# Alimentatore_Banco.net
KiCad netlist of a schematic drawn in EAGLE
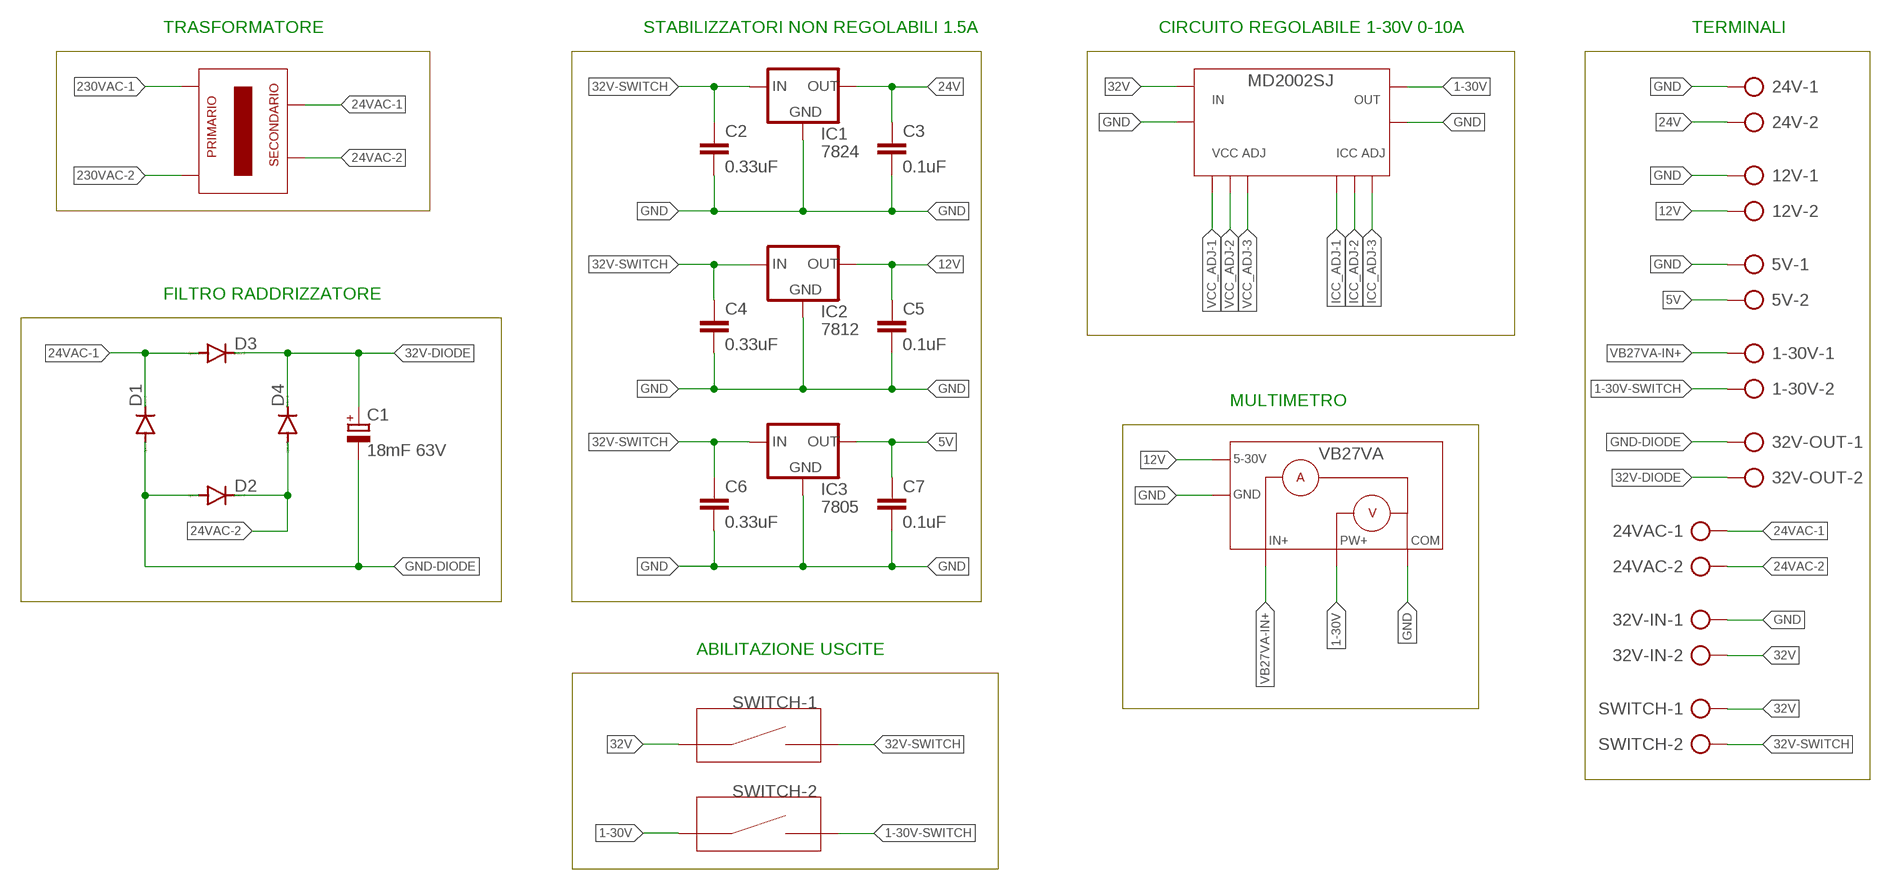
[diagram p0: schematic, sheet 1]

(export (version "E")
  (design (tool "Eeschema 10.0.6"))
  (components
    (comp (ref "1-30V")
      (value "SMKDSP_1,5/2")
      (footprint "eagle-import:SMKDSP_1,5_2")
      (fields (field (name "MF") "FARNELL") (field (name "MPN") "1733570"))
      (libsource (lib "eagle-import") (part "SMKDSP_1,5/2"))
    )
    (comp (ref "5V")
      (value "SMKDSP_1,5/2")
      (footprint "eagle-import:SMKDSP_1,5_2")
      (fields (field (name "MF") "FARNELL") (field (name "MPN") "1733570"))
      (libsource (lib "eagle-import") (part "SMKDSP_1,5/2"))
    )
    (comp (ref "12V")
      (value "SMKDSP_1,5/2")
      (footprint "eagle-import:SMKDSP_1,5_2")
      (fields (field (name "MF") "FARNELL") (field (name "MPN") "1733570"))
      (libsource (lib "eagle-import") (part "SMKDSP_1,5/2"))
    )
    (comp (ref "24V")
      (value "SMKDSP_1,5/2")
      (footprint "eagle-import:SMKDSP_1,5_2")
      (fields (field (name "MF") "FARNELL") (field (name "MPN") "1733570"))
      (libsource (lib "eagle-import") (part "SMKDSP_1,5/2"))
    )
    (comp (ref "24VAC")
      (value "SMKDSP_1,5/2")
      (footprint "eagle-import:SMKDSP_1,5_2")
      (fields (field (name "MF") "FARNELL") (field (name "MPN") "1733570"))
      (libsource (lib "eagle-import") (part "SMKDSP_1,5/2"))
    )
    (comp (ref "32V-IN")
      (value "SMKDSP_1,5/2")
      (footprint "eagle-import:SMKDSP_1,5_2")
      (fields (field (name "MF") "FARNELL") (field (name "MPN") "1733570"))
      (libsource (lib "eagle-import") (part "SMKDSP_1,5/2"))
    )
    (comp (ref "32V-OUT")
      (value "SMKDSP_1,5/2")
      (footprint "eagle-import:SMKDSP_1,5_2")
      (fields (field (name "MF") "FARNELL") (field (name "MPN") "1733570"))
      (libsource (lib "eagle-import") (part "SMKDSP_1,5/2"))
    )
    (comp (ref "C1")
      (value "18mF 63V")
      (footprint "eagle-import:E5-10,5")
      (libsource (lib "eagle-import") (part "CPOL-EUE5-10.5"))
    )
    (comp (ref "C2")
      (value "0.33uF")
      (footprint "eagle-import:C025-025X050")
      (libsource (lib "eagle-import") (part "C-EU025-025X050"))
    )
    (comp (ref "C3")
      (value "0.1uF")
      (footprint "eagle-import:C025-025X050")
      (libsource (lib "eagle-import") (part "C-EU025-025X050"))
    )
    (comp (ref "C4")
      (value "0.33uF")
      (footprint "eagle-import:C025-025X050")
      (libsource (lib "eagle-import") (part "C-EU025-025X050"))
    )
    (comp (ref "C5")
      (value "0.1uF")
      (footprint "eagle-import:C025-025X050")
      (libsource (lib "eagle-import") (part "C-EU025-025X050"))
    )
    (comp (ref "C6")
      (value "0.33uF")
      (footprint "eagle-import:C025-025X050")
      (libsource (lib "eagle-import") (part "C-EU025-025X050"))
    )
    (comp (ref "C7")
      (value "0.1uF")
      (footprint "eagle-import:C025-025X050")
      (libsource (lib "eagle-import") (part "C-EU025-025X050"))
    )
    (comp (ref "D1")
      (value "BY550")
      (footprint "eagle-import:DO27-15")
      (libsource (lib "eagle-import") (part "BY550"))
    )
    (comp (ref "D2")
      (value "BY550")
      (footprint "eagle-import:DO27-15")
      (libsource (lib "eagle-import") (part "BY550"))
    )
    (comp (ref "D3")
      (value "BY550")
      (footprint "eagle-import:DO27-15")
      (libsource (lib "eagle-import") (part "BY550"))
    )
    (comp (ref "D4")
      (value "BY550")
      (footprint "eagle-import:DO27-15")
      (libsource (lib "eagle-import") (part "BY550"))
    )
    (comp (ref "IC1")
      (value "7824")
      (footprint "eagle-import:78XXS")
      (libsource (lib "eagle-import") (part "78XXS"))
    )
    (comp (ref "IC2")
      (value "7812")
      (footprint "eagle-import:78XXS")
      (libsource (lib "eagle-import") (part "78XXS"))
    )
    (comp (ref "IC3")
      (value "7805")
      (footprint "eagle-import:78XXS")
      (libsource (lib "eagle-import") (part "78XXS"))
    )
    (comp (ref "SWITCH")
      (value "SMKDSP_1,5/2")
      (footprint "eagle-import:SMKDSP_1,5_2")
      (fields (field (name "MF") "FARNELL") (field (name "MPN") "1733570"))
      (libsource (lib "eagle-import") (part "SMKDSP_1,5/2"))
    )
  )
  (nets
    (net (code "2") (name "1-30V-SWITCH") (class "Default")
      (node (ref "1-30V") (pin "2") (pinfunction "KL_2") (pintype "passive"))
    )
    (net (code "3") (name "5V") (class "Default")
      (node (ref "5V") (pin "2") (pinfunction "KL_2") (pintype "passive"))
      (node (ref "C7") (pin "1") (pinfunction "1_1") (pintype "passive"))
      (node (ref "IC3") (pin "OUT") (pinfunction "OUT_OUT") (pintype "passive"))
    )
    (net (code "4") (name "12V") (class "Default")
      (node (ref "12V") (pin "2") (pinfunction "KL_2") (pintype "passive"))
      (node (ref "C5") (pin "1") (pinfunction "1_1") (pintype "passive"))
      (node (ref "IC2") (pin "OUT") (pinfunction "OUT_OUT") (pintype "passive"))
    )
    (net (code "5") (name "24V") (class "Default")
      (node (ref "24V") (pin "2") (pinfunction "KL_2") (pintype "passive"))
      (node (ref "C3") (pin "1") (pinfunction "1_1") (pintype "passive"))
      (node (ref "IC1") (pin "OUT") (pinfunction "OUT_OUT") (pintype "passive"))
    )
    (net (code "6") (name "24VAC-1") (class "Default")
      (node (ref "24VAC") (pin "1") (pinfunction "KL_1") (pintype "passive"))
      (node (ref "D1") (pin "C") (pinfunction "C_C") (pintype "passive"))
      (node (ref "D3") (pin "A") (pinfunction "A_A") (pintype "passive"))
    )
    (net (code "7") (name "24VAC-2") (class "Default")
      (node (ref "24VAC") (pin "2") (pinfunction "KL_2") (pintype "passive"))
      (node (ref "D2") (pin "C") (pinfunction "C_C") (pintype "passive"))
      (node (ref "D4") (pin "A") (pinfunction "A_A") (pintype "passive"))
    )
    (net (code "8") (name "32V") (class "Default")
      (node (ref "32V-IN") (pin "2") (pinfunction "KL_2") (pintype "passive"))
      (node (ref "SWITCH") (pin "1") (pinfunction "KL_1") (pintype "passive"))
    )
    (net (code "9") (name "32V-DIODE") (class "Default")
      (node (ref "32V-OUT") (pin "2") (pinfunction "KL_2") (pintype "passive"))
      (node (ref "C1") (pin "+") (pinfunction "+_+") (pintype "passive"))
      (node (ref "D3") (pin "C") (pinfunction "C_C") (pintype "passive"))
      (node (ref "D4") (pin "C") (pinfunction "C_C") (pintype "passive"))
    )
    (net (code "10") (name "32V-SWITCH") (class "Default")
      (node (ref "C2") (pin "1") (pinfunction "1_1") (pintype "passive"))
      (node (ref "C4") (pin "1") (pinfunction "1_1") (pintype "passive"))
      (node (ref "C6") (pin "1") (pinfunction "1_1") (pintype "passive"))
      (node (ref "IC1") (pin "IN") (pinfunction "IN_IN") (pintype "input"))
      (node (ref "IC2") (pin "IN") (pinfunction "IN_IN") (pintype "input"))
      (node (ref "IC3") (pin "IN") (pinfunction "IN_IN") (pintype "input"))
      (node (ref "SWITCH") (pin "2") (pinfunction "KL_2") (pintype "passive"))
    )
    (net (code "13") (name "GND") (class "Default")
      (node (ref "12V") (pin "1") (pinfunction "KL_1") (pintype "passive"))
      (node (ref "24V") (pin "1") (pinfunction "KL_1") (pintype "passive"))
      (node (ref "32V-IN") (pin "1") (pinfunction "KL_1") (pintype "passive"))
      (node (ref "5V") (pin "1") (pinfunction "KL_1") (pintype "passive"))
      (node (ref "C2") (pin "2") (pinfunction "2_2") (pintype "passive"))
      (node (ref "C3") (pin "2") (pinfunction "2_2") (pintype "passive"))
      (node (ref "C4") (pin "2") (pinfunction "2_2") (pintype "passive"))
      (node (ref "C5") (pin "2") (pinfunction "2_2") (pintype "passive"))
      (node (ref "C6") (pin "2") (pinfunction "2_2") (pintype "passive"))
      (node (ref "C7") (pin "2") (pinfunction "2_2") (pintype "passive"))
      (node (ref "IC1") (pin "GND") (pinfunction "GND_GND") (pintype "input"))
      (node (ref "IC2") (pin "GND") (pinfunction "GND_GND") (pintype "input"))
      (node (ref "IC3") (pin "GND") (pinfunction "GND_GND") (pintype "input"))
    )
    (net (code "14") (name "GND-DIODE") (class "Default")
      (node (ref "32V-OUT") (pin "1") (pinfunction "KL_1") (pintype "passive"))
      (node (ref "C1") (pin "-") (pinfunction "-_-") (pintype "passive"))
      (node (ref "D1") (pin "A") (pinfunction "A_A") (pintype "passive"))
      (node (ref "D2") (pin "A") (pinfunction "A_A") (pintype "passive"))
    )
    (net (code "18") (name "VB27VA-IN+") (class "Default")
      (node (ref "1-30V") (pin "1") (pinfunction "KL_1") (pintype "passive"))
    )
  )
)
